# Beacon.net
KiCad netlist of a schematic drawn in EAGLE
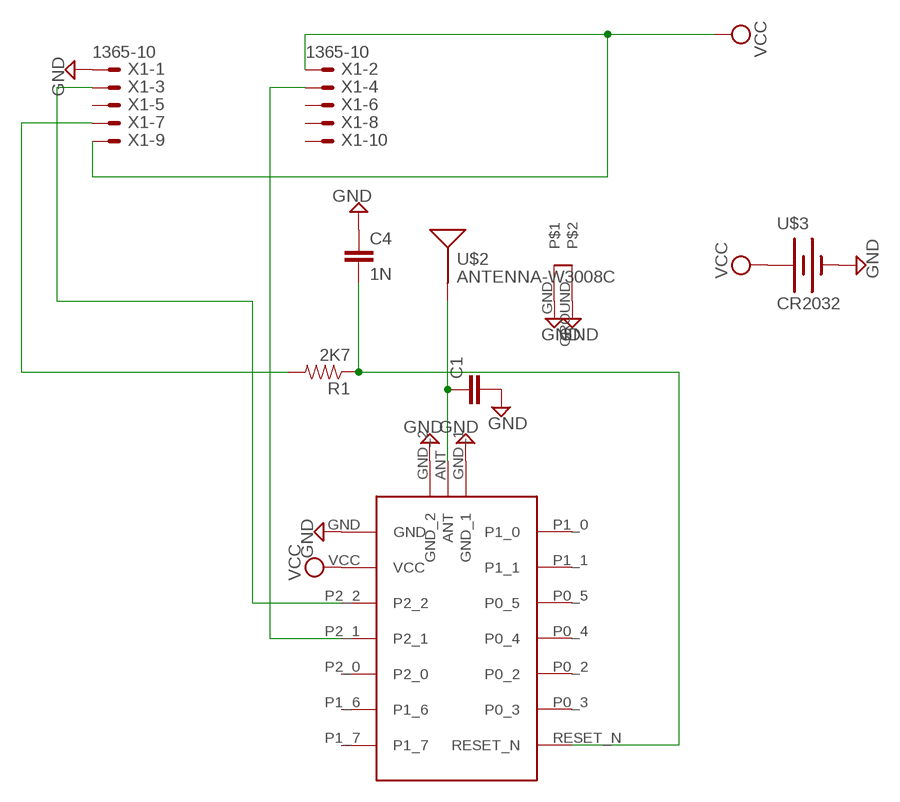
[diagram p0: schematic, sheet 1]

(export (version "E")
  (design (tool "Eeschema 10.0.6"))
  (components
    (comp (ref "C1")
      (value "CAP0402-CAP")
      (footprint "eagle-import:0402-CAP")
      (libsource (lib "eagle-import") (part "CAP0402-CAP"))
    )
    (comp (ref "C4")
      (value "1N")
      (footprint "eagle-import:0402-CAP")
      (libsource (lib "eagle-import") (part "CAP0402-CAP"))
    )
    (comp (ref "R1")
      (value "2K7")
      (footprint "eagle-import:0402-RES")
      (libsource (lib "eagle-import") (part "RESISTOR0402-RES"))
    )
    (comp (ref "U$1")
      (value "BLE4")
      (footprint "eagle-import:BLE4")
      (libsource (lib "eagle-import") (part "BLE4"))
    )
    (comp (ref "U$2")
      (value "ANTENNA-W3008C")
      (footprint "eagle-import:ANTENNA-W3008C")
      (libsource (lib "eagle-import") (part "ANTENNA-W3008C"))
    )
    (comp (ref "U$3")
      (value "CR2032")
      (footprint "eagle-import:BATTCON_2032")
      (libsource (lib "eagle-import") (part "CR2032"))
    )
    (comp (ref "X1")
      (value "1365-10")
      (footprint "eagle-import:1365-10")
      (libsource (lib "eagle-import") (part "1365-10"))
    )
  )
  (nets
    (net (code "1") (name "GND") (class "Default")
      (node (ref "C1") (pin "2") (pinfunction "2_2") (pintype "passive"))
      (node (ref "C4") (pin "1") (pinfunction "1_1") (pintype "passive"))
      (node (ref "U$1") (pin "GND") (pinfunction "GND_GND") (pintype "bidirectional"))
      (node (ref "U$1") (pin "GND_1") (pinfunction "GND_1_GND_1") (pintype "bidirectional"))
      (node (ref "U$1") (pin "GND_2") (pinfunction "GND_2_GND_2") (pintype "bidirectional"))
      (node (ref "U$2") (pin "GND") (pinfunction "P$1_GND") (pintype "bidirectional"))
      (node (ref "U$2") (pin "GROUND") (pinfunction "P$2_GROUND") (pintype "bidirectional"))
      (node (ref "U$3") (pin "PWR@2") (pinfunction "-_PWR@2") (pintype "power_in"))
      (node (ref "X1") (pin "1") (pinfunction "S_1") (pintype "passive"))
    )
    (net (code "2") (name "Net-(C4-Pad2)") (class "Default")
      (node (ref "C4") (pin "2") (pinfunction "2_2") (pintype "passive"))
      (node (ref "R1") (pin "1") (pinfunction "1_1") (pintype "passive"))
      (node (ref "U$1") (pin "RESET_N") (pinfunction "RESET_N_RESET_N") (pintype "bidirectional"))
    )
    (net (code "3") (name "Net-(U$2-SIGNAL)") (class "Default")
      (node (ref "C1") (pin "1") (pinfunction "1_1") (pintype "passive"))
      (node (ref "U$1") (pin "ANT") (pinfunction "ANT_ANT") (pintype "bidirectional"))
      (node (ref "U$2") (pin "FEED") (pinfunction "SIGNAL_FEED") (pintype "bidirectional"))
    )
    (net (code "4") (name "Net-(X1D-S)") (class "Default")
      (node (ref "U$1") (pin "P2_2") (pinfunction "P2_2_P2_2") (pintype "bidirectional"))
      (node (ref "X1") (pin "3") (pinfunction "S_3") (pintype "passive"))
    )
    (net (code "5") (name "Net-(X1E-S)") (class "Default")
      (node (ref "U$1") (pin "P2_1") (pinfunction "P2_1_P2_1") (pintype "bidirectional"))
      (node (ref "X1") (pin "4") (pinfunction "S_4") (pintype "passive"))
    )
    (net (code "6") (name "Net-(X1H-S)") (class "Default")
      (node (ref "R1") (pin "2") (pinfunction "2_2") (pintype "passive"))
      (node (ref "X1") (pin "7") (pinfunction "S_7") (pintype "passive"))
    )
    (net (code "7") (name "VCC") (class "Default")
      (node (ref "U$1") (pin "VCC") (pinfunction "VCC_VCC") (pintype "bidirectional"))
      (node (ref "U$3") (pin "PWR@1") (pinfunction "+_PWR@1") (pintype "power_in"))
      (node (ref "X1") (pin "2") (pinfunction "S_2") (pintype "passive"))
      (node (ref "X1") (pin "9") (pinfunction "S_9") (pintype "passive"))
    )
    (net (code "8") (name "unconnected-(U$1-PadP0_2)") (class "Default")
      (node (ref "U$1") (pin "P0_2") (pinfunction "P0_2_P0_2") (pintype "bidirectional"))
    )
    (net (code "9") (name "unconnected-(U$1-PadP0_3)") (class "Default")
      (node (ref "U$1") (pin "P0_3") (pinfunction "P0_3_P0_3") (pintype "bidirectional"))
    )
    (net (code "10") (name "unconnected-(U$1-PadP0_4)") (class "Default")
      (node (ref "U$1") (pin "P0_4") (pinfunction "P0_4_P0_4") (pintype "bidirectional"))
    )
    (net (code "11") (name "unconnected-(U$1-PadP0_5)") (class "Default")
      (node (ref "U$1") (pin "P0_5") (pinfunction "P0_5_P0_5") (pintype "bidirectional"))
    )
    (net (code "12") (name "unconnected-(U$1-PadP1_0)") (class "Default")
      (node (ref "U$1") (pin "P1_0") (pinfunction "P1_0_P1_0") (pintype "bidirectional"))
    )
    (net (code "13") (name "unconnected-(U$1-PadP1_1)") (class "Default")
      (node (ref "U$1") (pin "P1_1") (pinfunction "P1_1_P1_1") (pintype "bidirectional"))
    )
    (net (code "14") (name "unconnected-(U$1-PadP1_6)") (class "Default")
      (node (ref "U$1") (pin "P1_6") (pinfunction "P1_6_P1_6") (pintype "bidirectional"))
    )
    (net (code "15") (name "unconnected-(U$1-PadP1_7)") (class "Default")
      (node (ref "U$1") (pin "P1_7") (pinfunction "P1_7_P1_7") (pintype "bidirectional"))
    )
    (net (code "16") (name "unconnected-(U$1-PadP2_0)") (class "Default")
      (node (ref "U$1") (pin "P2_0") (pinfunction "P2_0_P2_0") (pintype "bidirectional"))
    )
    (net (code "17") (name "unconnected-(X1B-S-Pad10)") (class "Default")
      (node (ref "X1") (pin "10") (pinfunction "S_10") (pintype "passive"))
    )
    (net (code "18") (name "unconnected-(X1F-S-Pad5)") (class "Default")
      (node (ref "X1") (pin "5") (pinfunction "S_5") (pintype "passive"))
    )
    (net (code "19") (name "unconnected-(X1G-S-Pad6)") (class "Default")
      (node (ref "X1") (pin "6") (pinfunction "S_6") (pintype "passive"))
    )
    (net (code "20") (name "unconnected-(X1I-S-Pad8)") (class "Default")
      (node (ref "X1") (pin "8") (pinfunction "S_8") (pintype "passive"))
    )
  )
)
